# SC16IS740.net
KiCad netlist of a schematic drawn in Altium Designer
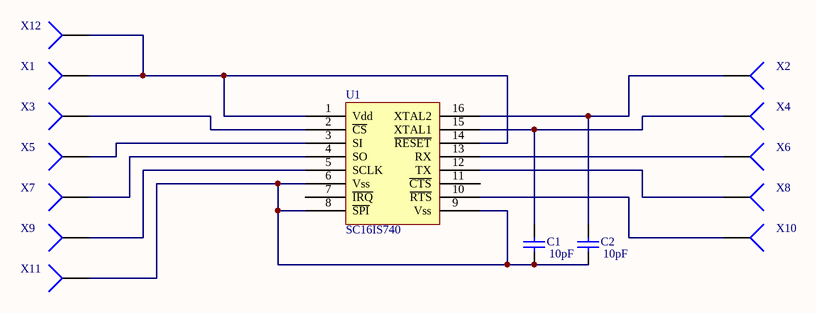
[diagram p0: SC16IS740.SchDoc]

(export (version "E")
  (design (tool "Eeschema 10.0.6"))
  (components
    (comp (ref "C1")
      (value "10pF")
      (footprint "_1206")
      (description "Capacitor")
      (fields (field (name "MANUFACTURER") "Generic Components") (field (name "PUBLISHER") "Altium Limited"))
      (libsource (lib "Miscellaneous Devices") (part "Cap Semi"))
    )
    (comp (ref "C2")
      (value "10pF")
      (footprint "_1206")
      (description "Capacitor")
      (fields (field (name "MANUFACTURER") "Generic Components") (field (name "PUBLISHER") "Altium Limited"))
      (libsource (lib "Miscellaneous Devices") (part "Cap Semi"))
    )
    (comp (ref "U1") (value "SC16IS740") (footprint "TSSO5X6-G16") (libsource (lib "PAL") (part "SC16IS740")))
    (comp (ref "X1")
      (value "~")
      (footprint "PIN1")
      (description "Socket")
      (fields (field (name "MANUFACTURER") "Generic Components") (field (name "PUBLISHER") "Altium Limited"))
      (libsource (lib "Miscellaneous Connectors") (part "Socket"))
    )
    (comp (ref "X2")
      (value "~")
      (footprint "PIN1")
      (description "Socket")
      (fields (field (name "MANUFACTURER") "Generic Components") (field (name "PUBLISHER") "Altium Limited"))
      (libsource (lib "Miscellaneous Connectors") (part "Socket"))
    )
    (comp (ref "X3")
      (value "~")
      (footprint "PIN1")
      (description "Socket")
      (fields (field (name "MANUFACTURER") "Generic Components") (field (name "PUBLISHER") "Altium Limited"))
      (libsource (lib "Miscellaneous Connectors") (part "Socket"))
    )
    (comp (ref "X4")
      (value "~")
      (footprint "PIN1")
      (description "Socket")
      (fields (field (name "MANUFACTURER") "Generic Components") (field (name "PUBLISHER") "Altium Limited"))
      (libsource (lib "Miscellaneous Connectors") (part "Socket"))
    )
    (comp (ref "X5")
      (value "~")
      (footprint "PIN1")
      (description "Socket")
      (fields (field (name "MANUFACTURER") "Generic Components") (field (name "PUBLISHER") "Altium Limited"))
      (libsource (lib "Miscellaneous Connectors") (part "Socket"))
    )
    (comp (ref "X6")
      (value "~")
      (footprint "PIN1")
      (description "Socket")
      (fields (field (name "MANUFACTURER") "Generic Components") (field (name "PUBLISHER") "Altium Limited"))
      (libsource (lib "Miscellaneous Connectors") (part "Socket"))
    )
    (comp (ref "X7")
      (value "~")
      (footprint "PIN1")
      (description "Socket")
      (fields (field (name "MANUFACTURER") "Generic Components") (field (name "PUBLISHER") "Altium Limited"))
      (libsource (lib "Miscellaneous Connectors") (part "Socket"))
    )
    (comp (ref "X8")
      (value "~")
      (footprint "PIN1")
      (description "Socket")
      (fields (field (name "MANUFACTURER") "Generic Components") (field (name "PUBLISHER") "Altium Limited"))
      (libsource (lib "Miscellaneous Connectors") (part "Socket"))
    )
    (comp (ref "X9")
      (value "~")
      (footprint "PIN1")
      (description "Socket")
      (fields (field (name "MANUFACTURER") "Generic Components") (field (name "PUBLISHER") "Altium Limited"))
      (libsource (lib "Miscellaneous Connectors") (part "Socket"))
    )
    (comp (ref "X10")
      (value "~")
      (footprint "PIN1")
      (description "Socket")
      (fields (field (name "MANUFACTURER") "Generic Components") (field (name "PUBLISHER") "Altium Limited"))
      (libsource (lib "Miscellaneous Connectors") (part "Socket"))
    )
    (comp (ref "X11")
      (value "~")
      (footprint "PIN1")
      (description "Socket")
      (fields (field (name "MANUFACTURER") "Generic Components") (field (name "PUBLISHER") "Altium Limited"))
      (libsource (lib "Miscellaneous Connectors") (part "Socket"))
    )
    (comp (ref "X12")
      (value "~")
      (footprint "PIN1")
      (description "Socket")
      (fields (field (name "MANUFACTURER") "Generic Components") (field (name "PUBLISHER") "Altium Limited"))
      (libsource (lib "Miscellaneous Connectors") (part "Socket"))
    )
  )
  (nets
    (net (code "1") (name "Net-(U1-RX)") (class "Default")
      (node (ref "U1") (pin "13") (pinfunction "RX_13") (pintype "passive"))
      (node (ref "X6") (pin "1") (pinfunction "1_1") (pintype "passive"))
    )
    (net (code "2") (name "Net-(U1-SCLK)") (class "Default")
      (node (ref "U1") (pin "5") (pinfunction "SCLK_5") (pintype "passive"))
      (node (ref "X9") (pin "1") (pinfunction "1_1") (pintype "passive"))
    )
    (net (code "3") (name "Net-(U1-SI)") (class "Default")
      (node (ref "U1") (pin "3") (pinfunction "SI_3") (pintype "passive"))
      (node (ref "X5") (pin "1") (pinfunction "1_1") (pintype "passive"))
    )
    (net (code "4") (name "Net-(U1-SO)") (class "Default")
      (node (ref "U1") (pin "4") (pinfunction "SO_4") (pintype "passive"))
      (node (ref "X7") (pin "1") (pinfunction "1_1") (pintype "passive"))
    )
    (net (code "5") (name "Net-(U1-TX)") (class "Default")
      (node (ref "U1") (pin "12") (pinfunction "TX_12") (pintype "passive"))
      (node (ref "X8") (pin "1") (pinfunction "1_1") (pintype "passive"))
    )
    (net (code "6") (name "Net-(U1-Vdd)") (class "Default")
      (node (ref "U1") (pin "1") (pinfunction "Vdd_1") (pintype "passive"))
      (node (ref "U1") (pin "14") (pinfunction "~{RESET}_14") (pintype "passive"))
      (node (ref "X1") (pin "1") (pinfunction "1_1") (pintype "passive"))
      (node (ref "X12") (pin "1") (pinfunction "1_1") (pintype "passive"))
    )
    (net (code "7") (name "Net-(U1-XTAL1)") (class "Default")
      (node (ref "C1") (pin "2") (pinfunction "2_2") (pintype "passive"))
      (node (ref "U1") (pin "15") (pinfunction "XTAL1_15") (pintype "passive"))
      (node (ref "X4") (pin "1") (pinfunction "1_1") (pintype "passive"))
    )
    (net (code "8") (name "Net-(U1-XTAL2)") (class "Default")
      (node (ref "C2") (pin "2") (pinfunction "2_2") (pintype "passive"))
      (node (ref "U1") (pin "16") (pinfunction "XTAL2_16") (pintype "passive"))
      (node (ref "X2") (pin "1") (pinfunction "1_1") (pintype "passive"))
    )
    (net (code "9") (name "Net-(U1-~{CS})") (class "Default")
      (node (ref "U1") (pin "2") (pinfunction "~{CS}_2") (pintype "passive"))
      (node (ref "X3") (pin "1") (pinfunction "1_1") (pintype "passive"))
    )
    (net (code "10") (name "Net-(U1-~{RTS})") (class "Default")
      (node (ref "U1") (pin "10") (pinfunction "~{RTS}_10") (pintype "passive"))
      (node (ref "X10") (pin "1") (pinfunction "1_1") (pintype "passive"))
    )
    (net (code "11") (name "Net-(U1-~{SPI})") (class "Default")
      (node (ref "C1") (pin "1") (pinfunction "1_1") (pintype "passive"))
      (node (ref "C2") (pin "1") (pinfunction "1_1") (pintype "passive"))
      (node (ref "U1") (pin "6") (pinfunction "Vss_6") (pintype "passive"))
      (node (ref "U1") (pin "8") (pinfunction "~{SPI}_8") (pintype "passive"))
      (node (ref "U1") (pin "9") (pinfunction "Vss_9") (pintype "passive"))
      (node (ref "X11") (pin "1") (pinfunction "1_1") (pintype "passive"))
    )
    (net (code "12") (name "unconnected-(U1-~{CTS}-Pad11)") (class "Default")
      (node (ref "U1") (pin "11") (pinfunction "~{CTS}_11") (pintype "passive"))
    )
    (net (code "13") (name "unconnected-(U1-~{IRQ}-Pad7)") (class "Default")
      (node (ref "U1") (pin "7") (pinfunction "~{IRQ}_7") (pintype "passive"))
    )
  )
)
